# DPT2_3.net
KiCad netlist of a schematic drawn in Altium Designer
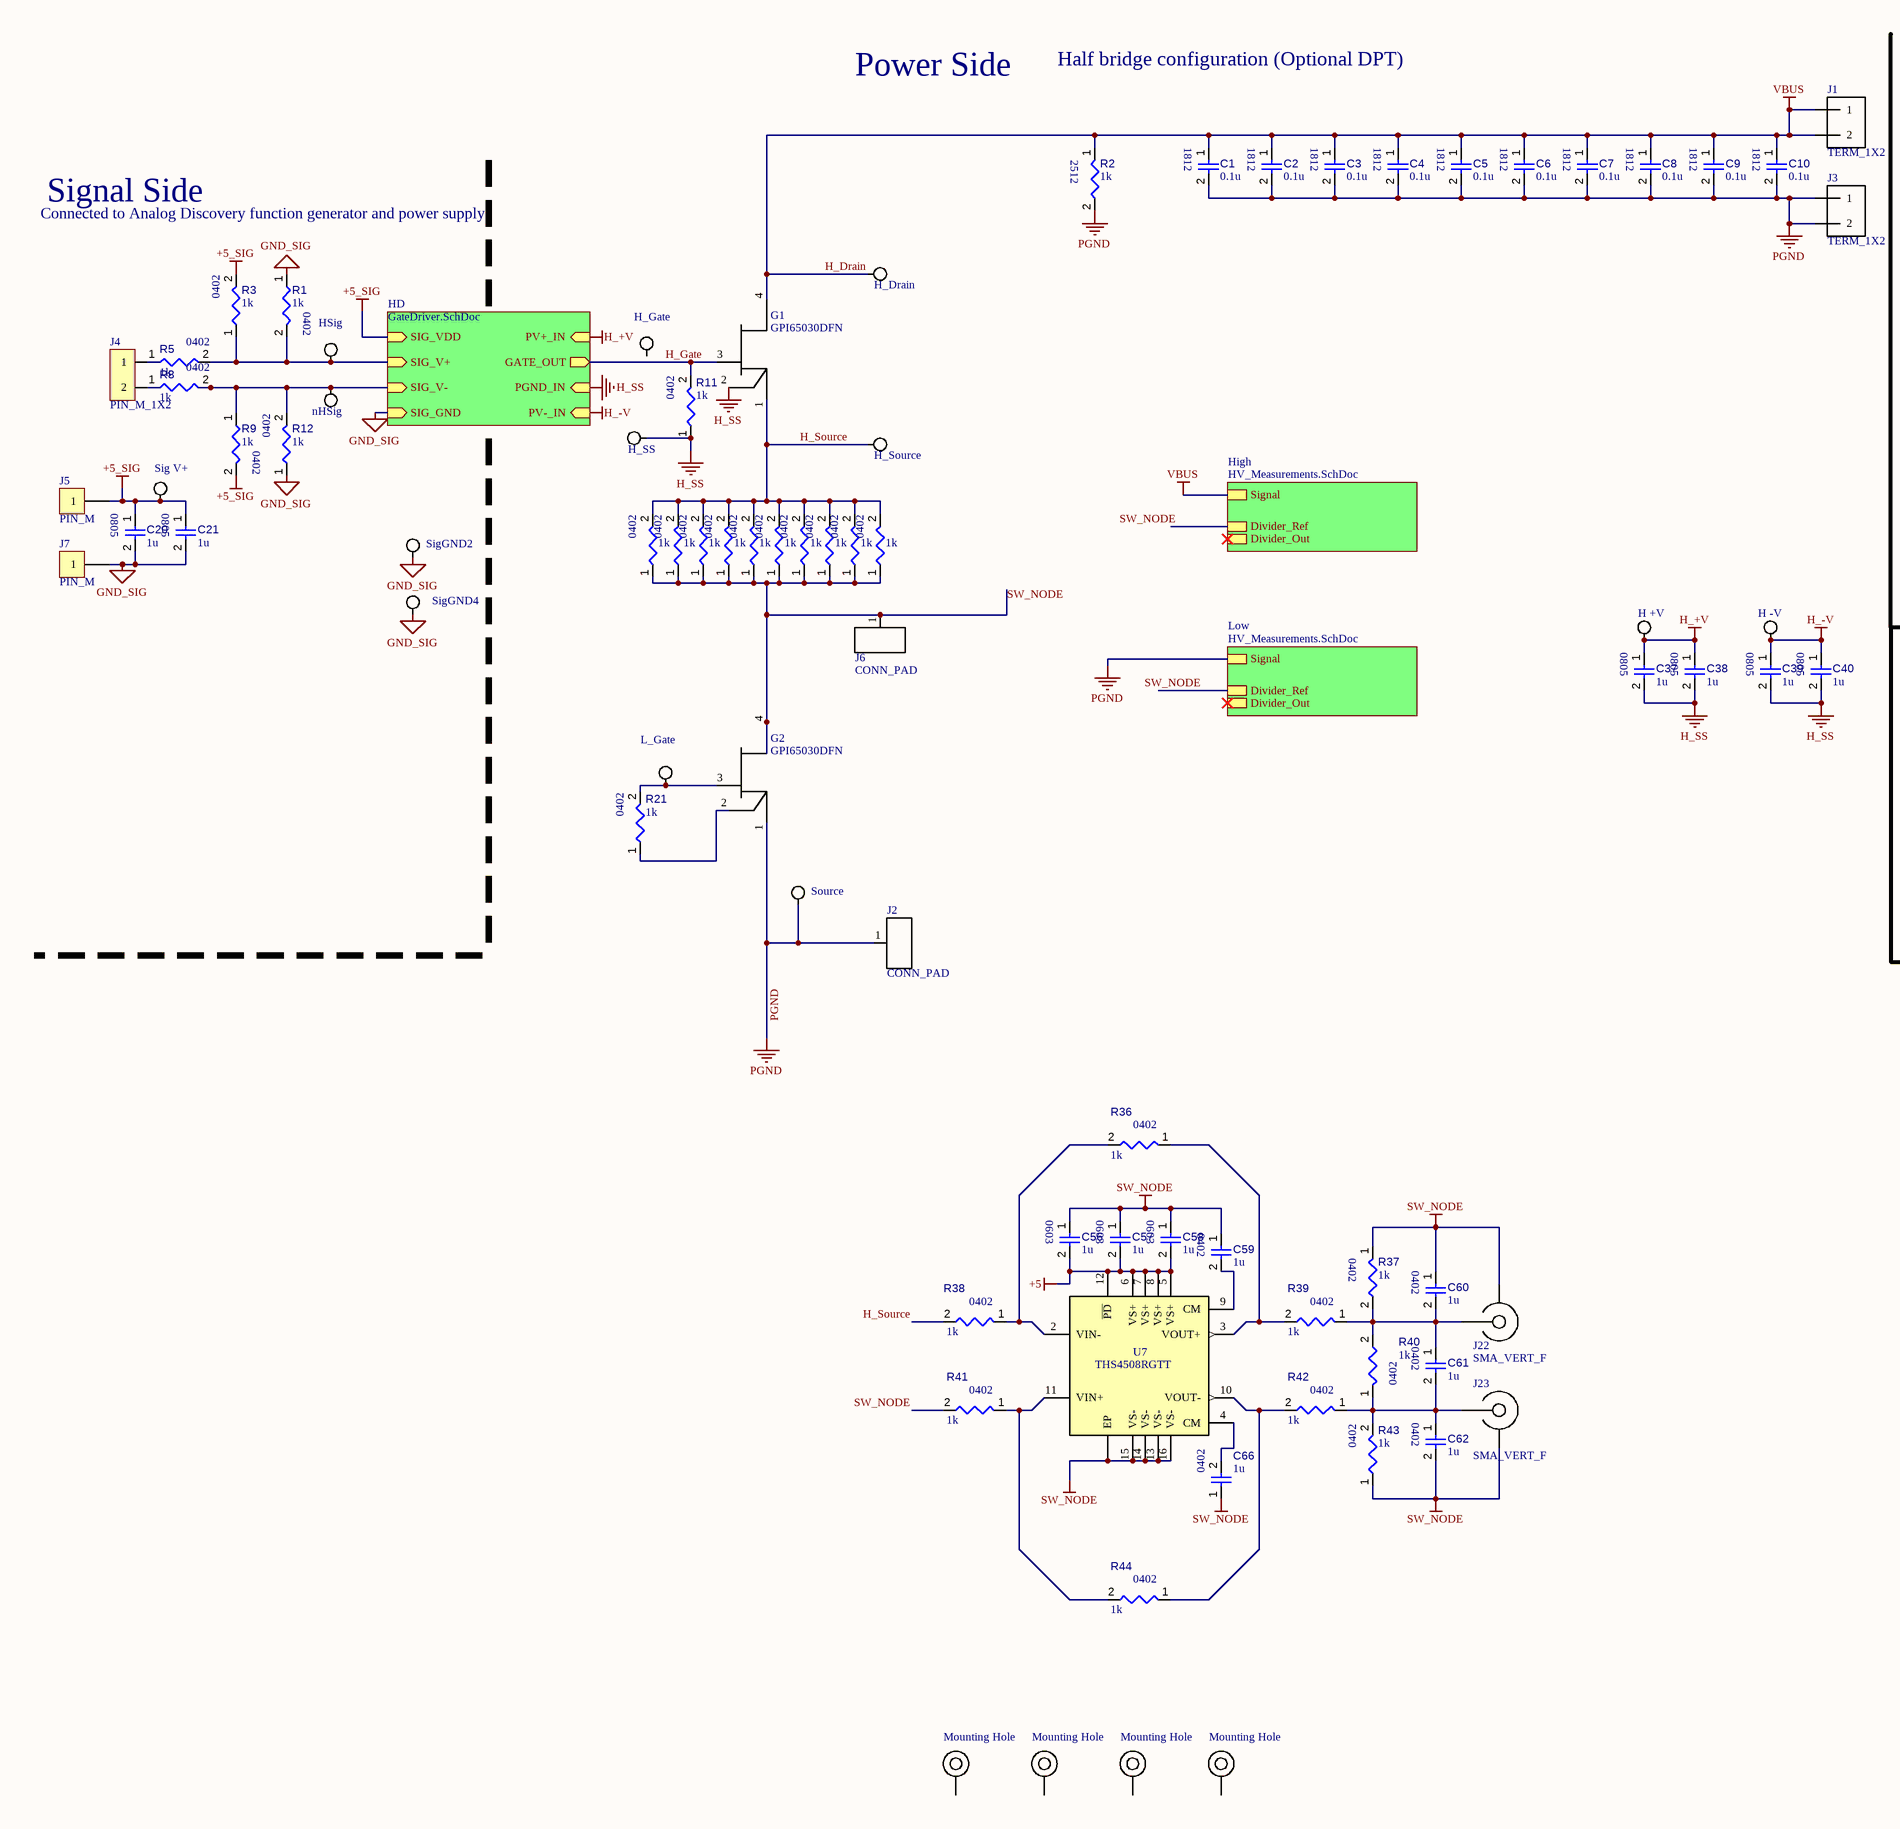
[diagram p0: DPT2.3.SchDoc, left]
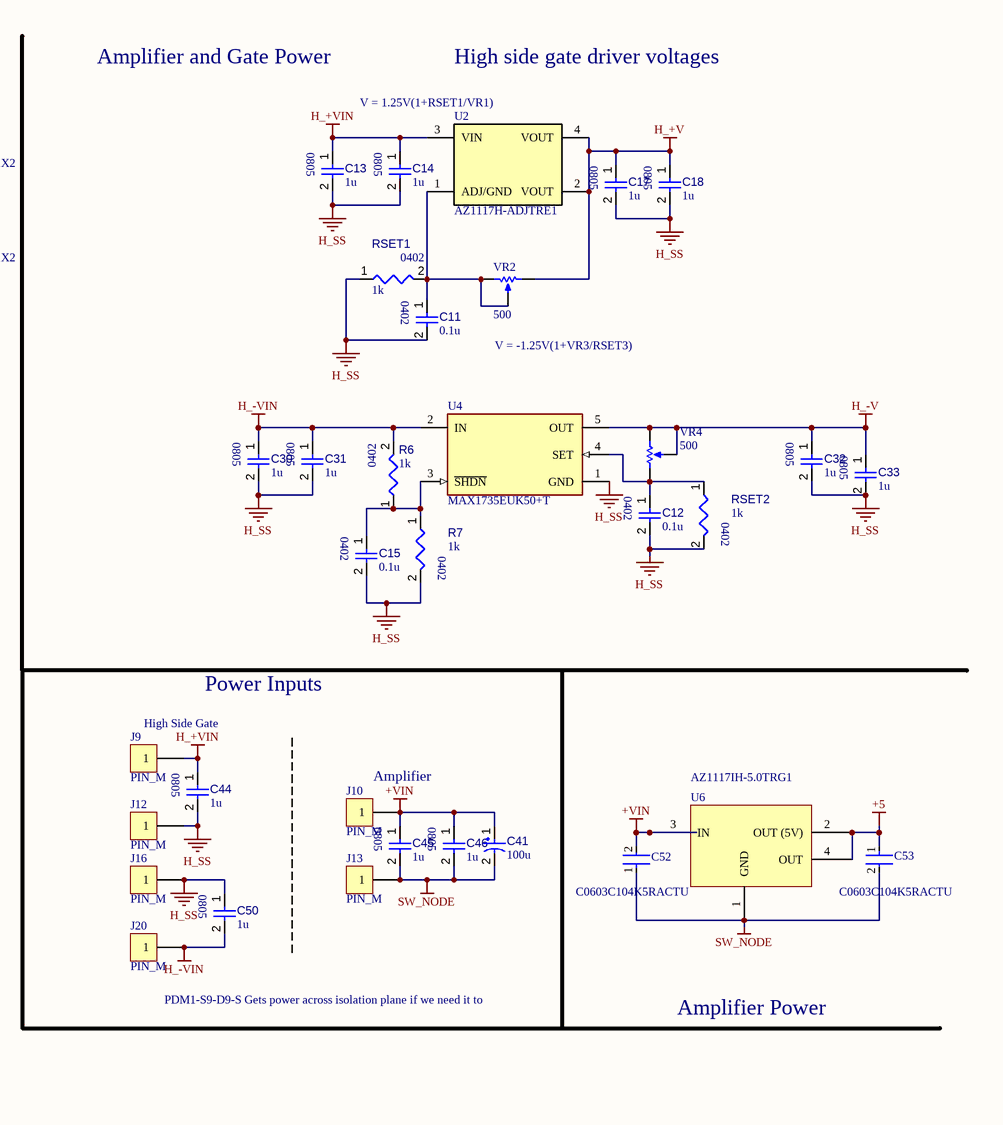
[diagram p1: DPT2.3.SchDoc, right]

(export (version "E")
  (design (tool "Eeschema 10.0.6"))
  (components
    (comp (ref "C1")
      (value "0.1u")
      (footprint "CAP_1812")
      (description "Non polarized SMD capacitor - 1812 (4532 Metric)")
      (fields (field (name "Comment") "CAP-1812"))
      (libsource (lib "2256-GaN Power") (part "CAP-NP-2"))
    )
    (comp (ref "C2")
      (value "0.1u")
      (footprint "CAP_1812")
      (description "Non polarized SMD capacitor - 1812 (4532 Metric)")
      (fields (field (name "Comment") "CAP-1812"))
      (libsource (lib "2256-GaN Power") (part "CAP-NP-2"))
    )
    (comp (ref "C3")
      (value "0.1u")
      (footprint "CAP_1812")
      (description "Non polarized SMD capacitor - 1812 (4532 Metric)")
      (fields (field (name "Comment") "CAP-1812"))
      (libsource (lib "2256-GaN Power") (part "CAP-NP-2"))
    )
    (comp (ref "C4")
      (value "0.1u")
      (footprint "CAP_1812")
      (description "Non polarized SMD capacitor - 1812 (4532 Metric)")
      (fields (field (name "Comment") "CAP-1812"))
      (libsource (lib "2256-GaN Power") (part "CAP-NP-2"))
    )
    (comp (ref "C5")
      (value "0.1u")
      (footprint "CAP_1812")
      (description "Non polarized SMD capacitor - 1812 (4532 Metric)")
      (fields (field (name "Comment") "CAP-1812"))
      (libsource (lib "2256-GaN Power") (part "CAP-NP-2"))
    )
    (comp (ref "C6")
      (value "0.1u")
      (footprint "CAP_1812")
      (description "Non polarized SMD capacitor - 1812 (4532 Metric)")
      (fields (field (name "Comment") "CAP-1812"))
      (libsource (lib "2256-GaN Power") (part "CAP-NP-2"))
    )
    (comp (ref "C7")
      (value "0.1u")
      (footprint "CAP_1812")
      (description "Non polarized SMD capacitor - 1812 (4532 Metric)")
      (fields (field (name "Comment") "CAP-1812"))
      (libsource (lib "2256-GaN Power") (part "CAP-NP-2"))
    )
    (comp (ref "C8")
      (value "0.1u")
      (footprint "CAP_1812")
      (description "Non polarized SMD capacitor - 1812 (4532 Metric)")
      (fields (field (name "Comment") "CAP-1812"))
      (libsource (lib "2256-GaN Power") (part "CAP-NP-2"))
    )
    (comp (ref "C9")
      (value "0.1u")
      (footprint "CAP_1812")
      (description "Non polarized SMD capacitor - 1812 (4532 Metric)")
      (fields (field (name "Comment") "CAP-1812"))
      (libsource (lib "2256-GaN Power") (part "CAP-NP-2"))
    )
    (comp (ref "C10")
      (value "0.1u")
      (footprint "CAP_1812")
      (description "Non polarized SMD capacitor - 1812 (4532 Metric)")
      (fields (field (name "Comment") "CAP-1812"))
      (libsource (lib "2256-GaN Power") (part "CAP-NP-2"))
    )
    (comp (ref "C11")
      (value "0.1u")
      (footprint "CAP_0402_HIGH")
      (description "Non polarized SMD capacitor - 0402 (1005 Metric)")
      (fields (field (name "Comment") "CAP-0402"))
      (libsource (lib "2256-GaN Power") (part "CAP-NP-2"))
    )
    (comp (ref "C12")
      (value "0.1u")
      (footprint "CAP_0402_HIGH")
      (description "Non polarized SMD capacitor - 0402 (1005 Metric)")
      (fields (field (name "Comment") "CAP-0402"))
      (libsource (lib "2256-GaN Power") (part "CAP-NP-2"))
    )
    (comp (ref "C13")
      (value "1u")
      (footprint "CAP_0805_MED")
      (description "Non polarized SMD capacitor - 0805 (1608 Metric)")
      (fields (field (name "Comment") "CAP-0805"))
      (libsource (lib "2256-GaN Power") (part "CAP-NP-2"))
    )
    (comp (ref "C14")
      (value "1u")
      (footprint "CAP_0805_MED")
      (description "Non polarized SMD capacitor - 0805 (1608 Metric)")
      (fields (field (name "Comment") "CAP-0805"))
      (libsource (lib "2256-GaN Power") (part "CAP-NP-2"))
    )
    (comp (ref "C15")
      (value "0.1u")
      (footprint "CAP_0402_HIGH")
      (description "Non polarized SMD capacitor - 0402 (1005 Metric)")
      (fields (field (name "Comment") "CAP-0402"))
      (libsource (lib "2256-GaN Power") (part "CAP-NP-2"))
    )
    (comp (ref "C17")
      (value "1u")
      (footprint "CAP_0805_MED")
      (description "Non polarized SMD capacitor - 0805 (1608 Metric)")
      (fields (field (name "Comment") "CAP-0805"))
      (libsource (lib "2256-GaN Power") (part "CAP-NP-2"))
    )
    (comp (ref "C18")
      (value "1u")
      (footprint "CAP_0805_MED")
      (description "Non polarized SMD capacitor - 0805 (1608 Metric)")
      (fields (field (name "Comment") "CAP-0805"))
      (libsource (lib "2256-GaN Power") (part "CAP-NP-2"))
    )
    (comp (ref "C20")
      (value "1u")
      (footprint "CAP_0805_MED")
      (description "Non polarized SMD capacitor - 0805 (1608 Metric)")
      (fields (field (name "Comment") "CAP-0805"))
      (libsource (lib "2256-GaN Power") (part "CAP-NP-2"))
    )
    (comp (ref "C21")
      (value "1u")
      (footprint "CAP_0805_MED")
      (description "Non polarized SMD capacitor - 0805 (1608 Metric)")
      (fields (field (name "Comment") "CAP-0805"))
      (libsource (lib "2256-GaN Power") (part "CAP-NP-2"))
    )
    (comp (ref "C30")
      (value "1u")
      (footprint "CAP_0805_MED")
      (description "Non polarized SMD capacitor - 0805 (1608 Metric)")
      (fields (field (name "Comment") "CAP-0805"))
      (libsource (lib "2256-GaN Power") (part "CAP-NP-2"))
    )
    (comp (ref "C31")
      (value "1u")
      (footprint "CAP_0805_MED")
      (description "Non polarized SMD capacitor - 0805 (1608 Metric)")
      (fields (field (name "Comment") "CAP-0805"))
      (libsource (lib "2256-GaN Power") (part "CAP-NP-2"))
    )
    (comp (ref "C32")
      (value "1u")
      (footprint "CAP_0805_MED")
      (description "Non polarized SMD capacitor - 0805 (1608 Metric)")
      (fields (field (name "Comment") "CAP-0805"))
      (libsource (lib "2256-GaN Power") (part "CAP-NP-2"))
    )
    (comp (ref "C33")
      (value "1u")
      (footprint "CAP_0805_MED")
      (description "Non polarized SMD capacitor - 0805 (1608 Metric)")
      (fields (field (name "Comment") "CAP-0805"))
      (libsource (lib "2256-GaN Power") (part "CAP-NP-2"))
    )
    (comp (ref "C37")
      (value "1u")
      (footprint "CAP_0805_MED")
      (description "Non polarized SMD capacitor - 0805 (1608 Metric)")
      (fields (field (name "Comment") "CAP-0805"))
      (libsource (lib "2256-GaN Power") (part "CAP-NP-2"))
    )
    (comp (ref "C38")
      (value "1u")
      (footprint "CAP_0805_MED")
      (description "Non polarized SMD capacitor - 0805 (1608 Metric)")
      (fields (field (name "Comment") "CAP-0805"))
      (libsource (lib "2256-GaN Power") (part "CAP-NP-2"))
    )
    (comp (ref "C39")
      (value "1u")
      (footprint "CAP_0805_MED")
      (description "Non polarized SMD capacitor - 0805 (1608 Metric)")
      (fields (field (name "Comment") "CAP-0805"))
      (libsource (lib "2256-GaN Power") (part "CAP-NP-2"))
    )
    (comp (ref "C40")
      (value "1u")
      (footprint "CAP_0805_MED")
      (description "Non polarized SMD capacitor - 0805 (1608 Metric)")
      (fields (field (name "Comment") "CAP-0805"))
      (libsource (lib "2256-GaN Power") (part "CAP-NP-2"))
    )
    (comp (ref "C41")
      (value "100u")
      (footprint "PCAP_2MM_5MM")
      (description "Polarized THT capacitor - Radial can, 2mm lead spacing, 5mm diameter")
      (fields (field (name "Comment") "PCAP-2MMx5MM"))
      (libsource (lib "2256-GaN Power") (part "CAP-P-2"))
    )
    (comp (ref "C44")
      (value "1u")
      (footprint "CAP_0805_MED")
      (description "Non polarized SMD capacitor - 0805 (1608 Metric)")
      (fields (field (name "Comment") "CAP-0805"))
      (libsource (lib "2256-GaN Power") (part "CAP-NP-2"))
    )
    (comp (ref "C45")
      (value "1u")
      (footprint "CAP_0805_MED")
      (description "Non polarized SMD capacitor - 0805 (1608 Metric)")
      (fields (field (name "Comment") "CAP-0805"))
      (libsource (lib "2256-GaN Power") (part "CAP-NP-2"))
    )
    (comp (ref "C46")
      (value "1u")
      (footprint "CAP_0805_MED")
      (description "Non polarized SMD capacitor - 0805 (1608 Metric)")
      (fields (field (name "Comment") "CAP-0805"))
      (libsource (lib "2256-GaN Power") (part "CAP-NP-2"))
    )
    (comp (ref "C50")
      (value "1u")
      (footprint "CAP_0805_MED")
      (description "Non polarized SMD capacitor - 0805 (1608 Metric)")
      (fields (field (name "Comment") "CAP-0805"))
      (libsource (lib "2256-GaN Power") (part "CAP-NP-2"))
    )
    (comp (ref "C52")
      (value "C0603C104K5RACTU")
      (footprint "FP-C0603C-CF-IPC_B")
      (description "CAP CER 0.1UF 50V X7R 0603")
      (fields (field (name "TOLERANCE") "0.1") (field (name "MANUFACTURER") "KEMET"))
      (libsource (lib "Altium Content Vault") (part "b4654b650e69147ec39a6b967a45e02"))
    )
    (comp (ref "C53")
      (value "C0603C104K5RACTU")
      (footprint "FP-C0603C-CF-IPC_B")
      (description "CAP CER 0.1UF 50V X7R 0603")
      (fields (field (name "TOLERANCE") "0.1") (field (name "MANUFACTURER") "KEMET"))
      (libsource (lib "Altium Content Vault") (part "b4654b650e69147ec39a6b967a45e02"))
    )
    (comp (ref "C56")
      (value "1u")
      (footprint "CAP_0603_HIGH")
      (description "Non polarized SMD capacitor - 0603 (1608 Metric)")
      (fields (field (name "Comment") "CAP-0603"))
      (libsource (lib "2256-GaN Power") (part "CAP-NP-2"))
    )
    (comp (ref "C57")
      (value "1u")
      (footprint "CAP_0603_HIGH")
      (description "Non polarized SMD capacitor - 0603 (1608 Metric)")
      (fields (field (name "Comment") "CAP-0603"))
      (libsource (lib "2256-GaN Power") (part "CAP-NP-2"))
    )
    (comp (ref "C58")
      (value "1u")
      (footprint "CAP_0603_HIGH")
      (description "Non polarized SMD capacitor - 0603 (1608 Metric)")
      (fields (field (name "Comment") "CAP-0603"))
      (libsource (lib "2256-GaN Power") (part "CAP-NP-2"))
    )
    (comp (ref "C59")
      (value "1u")
      (footprint "CAP_0402_HIGH")
      (description "Non polarized SMD capacitor - 0402 (1005 Metric)")
      (fields (field (name "Comment") "CAP-0402"))
      (libsource (lib "2256-GaN Power") (part "CAP-NP-2"))
    )
    (comp (ref "C60")
      (value "1u")
      (footprint "CAP_0402_HIGH")
      (description "Non polarized SMD capacitor - 0402 (1005 Metric)")
      (fields (field (name "Comment") "CAP-0402"))
      (libsource (lib "2256-GaN Power") (part "CAP-NP-2"))
    )
    (comp (ref "C61")
      (value "1u")
      (footprint "CAP_0402_HIGH")
      (description "Non polarized SMD capacitor - 0402 (1005 Metric)")
      (fields (field (name "Comment") "CAP-0402"))
      (libsource (lib "2256-GaN Power") (part "CAP-NP-2"))
    )
    (comp (ref "C62")
      (value "1u")
      (footprint "CAP_0402_HIGH")
      (description "Non polarized SMD capacitor - 0402 (1005 Metric)")
      (fields (field (name "Comment") "CAP-0402"))
      (libsource (lib "2256-GaN Power") (part "CAP-NP-2"))
    )
    (comp (ref "C66")
      (value "1u")
      (footprint "CAP_0402_HIGH")
      (description "Non polarized SMD capacitor - 0402 (1005 Metric)")
      (fields (field (name "Comment") "CAP-0402"))
      (libsource (lib "2256-GaN Power") (part "CAP-NP-2"))
    )
    (comp (ref "G1")
      (value "GPI65030DFN")
      (footprint "DFN_8X8")
      (description "650V 15A GaN Enhancement mode Transistor")
      (libsource (lib "2256-GaN Power") (part "TRANS_GPI65030DFN"))
    )
    (comp (ref "G2")
      (value "GPI65030DFN")
      (footprint "DFN_8X8")
      (description "650V 15A GaN Enhancement mode Transistor")
      (libsource (lib "2256-GaN Power") (part "TRANS_GPI65030DFN"))
    )
    (comp (ref "H +V")
      (value "Testpoint")
      (footprint "Testpoint-Footprint-1")
      (description "testpoint for circuit")
      (libsource (lib "2256-GaN Power") (part "Testpoint-Symbol-1"))
    )
    (comp (ref "H -V")
      (value "Testpoint")
      (footprint "Testpoint-Footprint-1")
      (description "testpoint for circuit")
      (libsource (lib "2256-GaN Power") (part "Testpoint-Symbol-1"))
    )
    (comp (ref "HSig")
      (value "Testpoint")
      (footprint "Testpoint-Footprint-1")
      (description "testpoint for circuit")
      (libsource (lib "2256-GaN Power") (part "Testpoint-Symbol-1"))
    )
    (comp (ref "H_Drain")
      (value "Testpoint")
      (footprint "Testpoint-Footprint-1")
      (description "testpoint for circuit")
      (libsource (lib "2256-GaN Power") (part "Testpoint-Symbol-1"))
    )
    (comp (ref "H_Gate")
      (value "Testpoint")
      (footprint "Testpoint-Footprint-1")
      (description "testpoint for circuit")
      (libsource (lib "2256-GaN Power") (part "Testpoint-Symbol-1"))
    )
    (comp (ref "H_Source")
      (value "Testpoint")
      (footprint "Testpoint-Footprint-1")
      (description "testpoint for circuit")
      (libsource (lib "2256-GaN Power") (part "Testpoint-Symbol-1"))
    )
    (comp (ref "H_SS")
      (value "Testpoint")
      (footprint "Testpoint-Footprint-1")
      (description "testpoint for circuit")
      (libsource (lib "2256-GaN Power") (part "Testpoint-Symbol-1"))
    )
    (comp (ref "J1")
      (value "TERM_1X2")
      (footprint "J_TERM_BLK_1X2")
      (description "Terminal Block 1X2, 6.35mm pitch")
      (libsource (lib "2256-GaN Power") (part "TERM_BLK_1X2"))
    )
    (comp (ref "J2")
      (value "CONN_PAD")
      (footprint "CONN_PAD")
      (description "Solderable Connection Pad")
      (libsource (lib "2256-GaN Power") (part "CONN_PAD"))
    )
    (comp (ref "J3")
      (value "TERM_1X2")
      (footprint "J_TERM_BLK_1X2")
      (description "Terminal Block 1X2, 6.35mm pitch")
      (libsource (lib "2256-GaN Power") (part "TERM_BLK_1X2"))
    )
    (comp (ref "J4")
      (value "PIN_M_1X2")
      (footprint "J_THT_2.54MM_1X2")
      (description "Male Pin 2.54mm pitch 1X2")
      (libsource (lib "2256-GaN Power") (part "M_PIN_HEAD_1X2"))
    )
    (comp (ref "J5")
      (value "PIN_M")
      (footprint "J_THT_1_PIN")
      (description "Male Pin, 1 Pin")
      (libsource (lib "2256-GaN Power") (part "M_PIN_HEAD_1X1"))
    )
    (comp (ref "J6")
      (value "CONN_PAD")
      (footprint "CONN_PAD")
      (description "Solderable Connection Pad")
      (libsource (lib "") (part "CONN_PAD_1"))
    )
    (comp (ref "J7")
      (value "PIN_M")
      (footprint "J_THT_1_PIN")
      (description "Male Pin, 1 Pin")
      (libsource (lib "2256-GaN Power") (part "M_PIN_HEAD_1X1"))
    )
    (comp (ref "J9")
      (value "PIN_M")
      (footprint "J_THT_1_PIN")
      (description "Male Pin, 1 Pin")
      (libsource (lib "2256-GaN Power") (part "M_PIN_HEAD_1X1"))
    )
    (comp (ref "J10")
      (value "PIN_M")
      (footprint "J_THT_1_PIN")
      (description "Male Pin, 1 Pin")
      (libsource (lib "2256-GaN Power") (part "M_PIN_HEAD_1X1"))
    )
    (comp (ref "J12")
      (value "PIN_M")
      (footprint "J_THT_1_PIN")
      (description "Male Pin, 1 Pin")
      (libsource (lib "2256-GaN Power") (part "M_PIN_HEAD_1X1"))
    )
    (comp (ref "J13")
      (value "PIN_M")
      (footprint "J_THT_1_PIN")
      (description "Male Pin, 1 Pin")
      (libsource (lib "2256-GaN Power") (part "M_PIN_HEAD_1X1"))
    )
    (comp (ref "J16")
      (value "PIN_M")
      (footprint "J_THT_1_PIN")
      (description "Male Pin, 1 Pin")
      (libsource (lib "2256-GaN Power") (part "M_PIN_HEAD_1X1"))
    )
    (comp (ref "J20")
      (value "PIN_M")
      (footprint "J_THT_1_PIN")
      (description "Male Pin, 1 Pin")
      (libsource (lib "2256-GaN Power") (part "M_PIN_HEAD_1X1"))
    )
    (comp (ref "J22")
      (value "SMA_VERT_F")
      (footprint "SMA_VERT_F")
      (description "SMA connector, Vertical, Female")
      (libsource (lib "") (part "SMA_F_1"))
    )
    (comp (ref "J23")
      (value "SMA_VERT_F")
      (footprint "SMA_VERT_F")
      (description "SMA connector, Vertical, Female")
      (libsource (lib "2256-GaN Power") (part "SMA_F"))
    )
    (comp (ref "L_Gate")
      (value "Testpoint")
      (footprint "Testpoint-Footprint-1")
      (description "testpoint for circuit")
      (libsource (lib "2256-GaN Power") (part "Testpoint-Symbol-1"))
    )
    (comp (ref "MH1")
      (value "Mounting Hole")
      (footprint "Mounting Hole-Footprint-1")
      (libsource (lib "2256-GaN Power") (part "Mounting Hole-Symbol-1"))
    )
    (comp (ref "MH2")
      (value "Mounting Hole")
      (footprint "Mounting Hole-Footprint-1")
      (libsource (lib "2256-GaN Power") (part "Mounting Hole-Symbol-1"))
    )
    (comp (ref "MH3")
      (value "Mounting Hole")
      (footprint "Mounting Hole-Footprint-1")
      (libsource (lib "2256-GaN Power") (part "Mounting Hole-Symbol-1"))
    )
    (comp (ref "MH4")
      (value "Mounting Hole")
      (footprint "Mounting Hole-Footprint-1")
      (libsource (lib "2256-GaN Power") (part "Mounting Hole-Symbol-1"))
    )
    (comp (ref "nHSig")
      (value "Testpoint")
      (footprint "Testpoint-Footprint-1")
      (description "testpoint for circuit")
      (libsource (lib "2256-GaN Power") (part "Testpoint-Symbol-1"))
    )
    (comp (ref "R1")
      (value "1k")
      (footprint "RES_0402_HIGH")
      (description "SMD Resistor - 0402 (1005 Metric)")
      (fields (field (name "Comment") "RES-0402"))
      (libsource (lib "2256-GaN Power") (part "RES-2"))
    )
    (comp (ref "R2")
      (value "1k")
      (footprint "RES_2512_MED")
      (description "SMD Resistor - 2512 (6432 Metric)")
      (fields (field (name "Comment") "RES-2512"))
      (libsource (lib "2256-GaN Power") (part "RES-2"))
    )
    (comp (ref "R3")
      (value "1k")
      (footprint "RES_0402_HIGH")
      (description "SMD Resistor - 0402 (1005 Metric)")
      (fields (field (name "Comment") "RES-0402"))
      (libsource (lib "2256-GaN Power") (part "RES-2"))
    )
    (comp (ref "R4")
      (value "1k")
      (footprint "RES_0402_HIGH")
      (description "SMD Resistor - 0402 (1005 Metric)")
      (fields (field (name "Comment") "RES-0402"))
      (libsource (lib "2256-GaN Power") (part "RES-2"))
    )
    (comp (ref "R5")
      (value "1k")
      (footprint "RES_0402_HIGH")
      (description "SMD Resistor - 0402 (1005 Metric)")
      (fields (field (name "Comment") "RES-0402"))
      (libsource (lib "2256-GaN Power") (part "RES-2"))
    )
    (comp (ref "R6")
      (value "1k")
      (footprint "RES_0402_HIGH")
      (description "SMD Resistor - 0402 (1005 Metric)")
      (fields (field (name "Comment") "RES-0402"))
      (libsource (lib "2256-GaN Power") (part "RES-2"))
    )
    (comp (ref "R7")
      (value "1k")
      (footprint "RES_0402_HIGH")
      (description "SMD Resistor - 0402 (1005 Metric)")
      (fields (field (name "Comment") "RES-0402"))
      (libsource (lib "2256-GaN Power") (part "RES-2"))
    )
    (comp (ref "R8")
      (value "1k")
      (footprint "RES_0402_HIGH")
      (description "SMD Resistor - 0402 (1005 Metric)")
      (fields (field (name "Comment") "RES-0402"))
      (libsource (lib "2256-GaN Power") (part "RES-2"))
    )
    (comp (ref "R9")
      (value "1k")
      (footprint "RES_0402_HIGH")
      (description "SMD Resistor - 0402 (1005 Metric)")
      (fields (field (name "Comment") "RES-0402"))
      (libsource (lib "2256-GaN Power") (part "RES-2"))
    )
    (comp (ref "R10")
      (value "1k")
      (footprint "RES_0402_HIGH")
      (description "SMD Resistor - 0402 (1005 Metric)")
      (fields (field (name "Comment") "RES-0402"))
      (libsource (lib "2256-GaN Power") (part "RES-2"))
    )
    (comp (ref "R11")
      (value "1k")
      (footprint "RES_0402_HIGH")
      (description "SMD Resistor - 0402 (1005 Metric)")
      (fields (field (name "Comment") "RES-0402"))
      (libsource (lib "2256-GaN Power") (part "RES-2"))
    )
    (comp (ref "R12")
      (value "1k")
      (footprint "RES_0402_HIGH")
      (description "SMD Resistor - 0402 (1005 Metric)")
      (fields (field (name "Comment") "RES-0402"))
      (libsource (lib "2256-GaN Power") (part "RES-2"))
    )
    (comp (ref "R21")
      (value "1k")
      (footprint "RES_0402_HIGH")
      (description "SMD Resistor - 0402 (1005 Metric)")
      (fields (field (name "Comment") "RES-0402"))
      (libsource (lib "2256-GaN Power") (part "RES-2"))
    )
    (comp (ref "R23")
      (value "1k")
      (footprint "RES_0402_HIGH")
      (description "SMD Resistor - 0402 (1005 Metric)")
      (fields (field (name "Comment") "RES-0402"))
      (libsource (lib "2256-GaN Power") (part "RES-2"))
    )
    (comp (ref "R25")
      (value "1k")
      (footprint "RES_0402_HIGH")
      (description "SMD Resistor - 0402 (1005 Metric)")
      (fields (field (name "Comment") "RES-0402"))
      (libsource (lib "2256-GaN Power") (part "RES-2"))
    )
    (comp (ref "R36")
      (value "1k")
      (footprint "RES_0402_HIGH")
      (description "SMD Resistor - 0402 (1005 Metric)")
      (fields (field (name "Comment") "RES-0402"))
      (libsource (lib "2256-GaN Power") (part "RES-2"))
    )
    (comp (ref "R37")
      (value "1k")
      (footprint "RES_0402_HIGH")
      (description "SMD Resistor - 0402 (1005 Metric)")
      (fields (field (name "Comment") "RES-0402"))
      (libsource (lib "2256-GaN Power") (part "RES-2"))
    )
    (comp (ref "R38")
      (value "1k")
      (footprint "RES_0402_HIGH")
      (description "SMD Resistor - 0402 (1005 Metric)")
      (fields (field (name "Comment") "RES-0402"))
      (libsource (lib "2256-GaN Power") (part "RES-2"))
    )
    (comp (ref "R39")
      (value "1k")
      (footprint "RES_0402_HIGH")
      (description "SMD Resistor - 0402 (1005 Metric)")
      (fields (field (name "Comment") "RES-0402"))
      (libsource (lib "2256-GaN Power") (part "RES-2"))
    )
    (comp (ref "R40")
      (value "1k")
      (footprint "RES_0402_HIGH")
      (description "SMD Resistor - 0402 (1005 Metric)")
      (fields (field (name "Comment") "RES-0402"))
      (libsource (lib "2256-GaN Power") (part "RES-2"))
    )
    (comp (ref "R41")
      (value "1k")
      (footprint "RES_0402_HIGH")
      (description "SMD Resistor - 0402 (1005 Metric)")
      (fields (field (name "Comment") "RES-0402"))
      (libsource (lib "2256-GaN Power") (part "RES-2"))
    )
    (comp (ref "R42")
      (value "1k")
      (footprint "RES_0402_HIGH")
      (description "SMD Resistor - 0402 (1005 Metric)")
      (fields (field (name "Comment") "RES-0402"))
      (libsource (lib "2256-GaN Power") (part "RES-2"))
    )
    (comp (ref "R43")
      (value "1k")
      (footprint "RES_0402_HIGH")
      (description "SMD Resistor - 0402 (1005 Metric)")
      (fields (field (name "Comment") "RES-0402"))
      (libsource (lib "2256-GaN Power") (part "RES-2"))
    )
    (comp (ref "R44")
      (value "1k")
      (footprint "RES_0402_HIGH")
      (description "SMD Resistor - 0402 (1005 Metric)")
      (fields (field (name "Comment") "RES-0402"))
      (libsource (lib "2256-GaN Power") (part "RES-2"))
    )
    (comp (ref "R45")
      (value "1k")
      (footprint "RES_0402_HIGH")
      (description "SMD Resistor - 0402 (1005 Metric)")
      (fields (field (name "Comment") "RES-0402"))
      (libsource (lib "2256-GaN Power") (part "RES-2"))
    )
    (comp (ref "R46")
      (value "1k")
      (footprint "RES_0402_HIGH")
      (description "SMD Resistor - 0402 (1005 Metric)")
      (fields (field (name "Comment") "RES-0402"))
      (libsource (lib "2256-GaN Power") (part "RES-2"))
    )
    (comp (ref "R47")
      (value "1k")
      (footprint "RES_0402_HIGH")
      (description "SMD Resistor - 0402 (1005 Metric)")
      (fields (field (name "Comment") "RES-0402"))
      (libsource (lib "2256-GaN Power") (part "RES-2"))
    )
    (comp (ref "R49")
      (value "1k")
      (footprint "RES_0402_HIGH")
      (description "SMD Resistor - 0402 (1005 Metric)")
      (fields (field (name "Comment") "RES-0402"))
      (libsource (lib "2256-GaN Power") (part "RES-2"))
    )
    (comp (ref "R50")
      (value "1k")
      (footprint "RES_0402_HIGH")
      (description "SMD Resistor - 0402 (1005 Metric)")
      (fields (field (name "Comment") "RES-0402"))
      (libsource (lib "2256-GaN Power") (part "RES-2"))
    )
    (comp (ref "R53")
      (value "1k")
      (footprint "RES_0402_HIGH")
      (description "SMD Resistor - 0402 (1005 Metric)")
      (fields (field (name "Comment") "RES-0402"))
      (libsource (lib "2256-GaN Power") (part "RES-2"))
    )
    (comp (ref "RSET1")
      (value "1k")
      (footprint "RES_0402_HIGH")
      (description "SMD Resistor - 0402 (1005 Metric)")
      (fields (field (name "Comment") "RES-0402"))
      (libsource (lib "2256-GaN Power") (part "RES-2"))
    )
    (comp (ref "RSET2")
      (value "1k")
      (footprint "RES_0402_HIGH")
      (description "SMD Resistor - 0402 (1005 Metric)")
      (fields (field (name "Comment") "RES-0402"))
      (libsource (lib "2256-GaN Power") (part "RES-2"))
    )
    (comp (ref "Sig V+")
      (value "Testpoint")
      (footprint "Testpoint-Footprint-1")
      (description "testpoint for circuit")
      (libsource (lib "2256-GaN Power") (part "Testpoint-Symbol-1"))
    )
    (comp (ref "SigGND2")
      (value "Testpoint")
      (footprint "Testpoint-Footprint-1")
      (description "testpoint for circuit")
      (libsource (lib "2256-GaN Power") (part "Testpoint-Symbol-1"))
    )
    (comp (ref "SigGND4")
      (value "Testpoint")
      (footprint "Testpoint-Footprint-1")
      (description "testpoint for circuit")
      (libsource (lib "2256-GaN Power") (part "Testpoint-Symbol-1"))
    )
    (comp (ref "Source")
      (value "Testpoint")
      (footprint "Testpoint-Footprint-1")
      (description "testpoint for circuit")
      (libsource (lib "2256-GaN Power") (part "Testpoint-Symbol-1"))
    )
    (comp (ref "U2")
      (value "AZ1117H-ADJTRE1")
      (footprint "SOT-223")
      (description "IC REG LINEAR POS ADJ 1A SOT223")
      (libsource (lib "2256-GaN Power") (part "AZ1117H-ADJTRE1"))
    )
    (comp (ref "U4")
      (value "MAX1735EUK50+T")
      (footprint "FP-U5-2-IPC_B")
      (description "IC REG LIN NEG ADJ 200MA SOT23-5")
      (libsource (lib "Altium Content Vault") (part "3fe5ddc4f403acdf696fd8e1856eecf"))
    )
    (comp (ref "U6")
      (value "AZ1117IH-5.0TRG1")
      (footprint "SOT230P700X180-4N")
      (description "https://www.digikey.ca/en/products/detail/diodes-incorporated/AZ1117IH-5-0TRG1/5699673")
      (libsource (lib "2256-GaN Power") (part "AZ1117IH-5.0TRG1-Symbol-1"))
    )
    (comp (ref "U7")
      (value "THS4508RGTT")
      (footprint "QFN-16")
      (description "WIDEBAND, LOW NOISE, LOW DISTORTION FULLY DIFFERENTIAL AMPLIFIER")
      (libsource (lib "2256-GaN Power") (part "THS4508"))
    )
    (comp (ref "VR2")
      (value "500")
      (footprint "TRIM_J-LEAD")
      (description "Potentiometer, J-Lead Trim Pot")
      (fields (field (name "Comment") "RES_POT_JLEAD"))
      (libsource (lib "2256-GaN Power") (part "RES-POT-3"))
    )
    (comp (ref "VR4")
      (value "500")
      (footprint "TRIM_J-LEAD")
      (description "Potentiometer, J-Lead Trim Pot")
      (fields (field (name "Comment") "RES_POT_JLEAD"))
      (libsource (lib "2256-GaN Power") (part "RES-POT-3"))
    )
  )
  (nets
    (net (code "1") (name "+5") (class "Default")
      (node (ref "C53") (pin "1") (pinfunction "1_1") (pintype "passive"))
      (node (ref "C56") (pin "2") (pinfunction "2_2") (pintype "passive"))
      (node (ref "C57") (pin "2") (pinfunction "2_2") (pintype "passive"))
      (node (ref "C58") (pin "2") (pinfunction "2_2") (pintype "passive"))
      (node (ref "U6") (pin "2") (pinfunction "OUT_(5V)_2") (pintype "passive"))
      (node (ref "U6") (pin "4") (pinfunction "OUT_4") (pintype "passive"))
      (node (ref "U7") (pin "12") (pinfunction "~{PD}_12") (pintype "passive"))
      (node (ref "U7") (pin "5") (pinfunction "VS+_5") (pintype "power_in"))
      (node (ref "U7") (pin "6") (pinfunction "VS+_6") (pintype "power_in"))
      (node (ref "U7") (pin "7") (pinfunction "VS+_7") (pintype "power_in"))
      (node (ref "U7") (pin "8") (pinfunction "VS+_8") (pintype "power_in"))
    )
    (net (code "2") (name "+5_SIG") (class "Default")
      (node (ref "C20") (pin "1") (pinfunction "1_1") (pintype "passive"))
      (node (ref "C21") (pin "1") (pinfunction "1_1") (pintype "passive"))
      (node (ref "J5") (pin "1") (pinfunction "1_1") (pintype "passive"))
      (node (ref "R3") (pin "2") (pinfunction "2_2") (pintype "passive"))
      (node (ref "R9") (pin "2") (pinfunction "2_2") (pintype "passive"))
      (node (ref "Sig V+") (pin "1") (pinfunction "1_1") (pintype "passive"))
    )
    (net (code "3") (name "+VIN") (class "Default")
      (node (ref "C41") (pin "1") (pinfunction "1_1") (pintype "passive"))
      (node (ref "C45") (pin "1") (pinfunction "1_1") (pintype "passive"))
      (node (ref "C46") (pin "1") (pinfunction "1_1") (pintype "passive"))
      (node (ref "C52") (pin "2") (pinfunction "2_2") (pintype "passive"))
      (node (ref "J10") (pin "1") (pinfunction "1_1") (pintype "passive"))
      (node (ref "U6") (pin "3") (pinfunction "IN_3") (pintype "passive"))
    )
    (net (code "6") (name "/H_Gate") (class "Default")
      (node (ref "G1") (pin "3") (pinfunction "G_3") (pintype "passive"))
      (node (ref "R11") (pin "2") (pinfunction "2_2") (pintype "passive"))
    )
    (net (code "7") (name "/H_Source") (class "Default")
      (node (ref "G1") (pin "1") (pinfunction "S_1") (pintype "passive"))
      (node (ref "H_Source") (pin "1") (pinfunction "1_1") (pintype "passive"))
      (node (ref "R10") (pin "2") (pinfunction "2_2") (pintype "passive"))
      (node (ref "R23") (pin "2") (pinfunction "2_2") (pintype "passive"))
      (node (ref "R25") (pin "2") (pinfunction "2_2") (pintype "passive"))
      (node (ref "R38") (pin "2") (pinfunction "2_2") (pintype "passive"))
      (node (ref "R4") (pin "2") (pinfunction "2_2") (pintype "passive"))
      (node (ref "R45") (pin "2") (pinfunction "2_2") (pintype "passive"))
      (node (ref "R46") (pin "2") (pinfunction "2_2") (pintype "passive"))
      (node (ref "R47") (pin "2") (pinfunction "2_2") (pintype "passive"))
      (node (ref "R49") (pin "2") (pinfunction "2_2") (pintype "passive"))
      (node (ref "R50") (pin "2") (pinfunction "2_2") (pintype "passive"))
      (node (ref "R53") (pin "2") (pinfunction "2_2") (pintype "passive"))
    )
    (net (code "8") (name "/SIG_V+") (class "Default")
      (node (ref "HSig") (pin "1") (pinfunction "1_1") (pintype "passive"))
      (node (ref "R1") (pin "2") (pinfunction "2_2") (pintype "passive"))
      (node (ref "R3") (pin "1") (pinfunction "1_1") (pintype "passive"))
      (node (ref "R5") (pin "2") (pinfunction "2_2") (pintype "passive"))
    )
    (net (code "9") (name "/SIG_V-") (class "Default")
      (node (ref "R12") (pin "2") (pinfunction "2_2") (pintype "passive"))
      (node (ref "R8") (pin "2") (pinfunction "2_2") (pintype "passive"))
      (node (ref "R9") (pin "1") (pinfunction "1_1") (pintype "passive"))
      (node (ref "nHSig") (pin "1") (pinfunction "1_1") (pintype "passive"))
    )
    (net (code "10") (name "GND_SIG") (class "Default")
      (node (ref "C20") (pin "2") (pinfunction "2_2") (pintype "passive"))
      (node (ref "C21") (pin "2") (pinfunction "2_2") (pintype "passive"))
      (node (ref "J7") (pin "1") (pinfunction "1_1") (pintype "passive"))
      (node (ref "R1") (pin "1") (pinfunction "1_1") (pintype "passive"))
      (node (ref "R12") (pin "1") (pinfunction "1_1") (pintype "passive"))
      (node (ref "SigGND2") (pin "1") (pinfunction "1_1") (pintype "passive"))
      (node (ref "SigGND4") (pin "1") (pinfunction "1_1") (pintype "passive"))
    )
    (net (code "11") (name "H_+V") (class "Default")
      (node (ref "C17") (pin "1") (pinfunction "1_1") (pintype "passive"))
      (node (ref "C18") (pin "1") (pinfunction "1_1") (pintype "passive"))
      (node (ref "C37") (pin "1") (pinfunction "1_1") (pintype "passive"))
      (node (ref "C38") (pin "1") (pinfunction "1_1") (pintype "passive"))
      (node (ref "H +V") (pin "1") (pinfunction "1_1") (pintype "passive"))
      (node (ref "U2") (pin "2") (pinfunction "VOUT_2") (pintype "passive"))
      (node (ref "U2") (pin "4") (pinfunction "VOUT_4") (pintype "passive"))
      (node (ref "VR2") (pin "1") (pinfunction "CCW_1") (pintype "passive"))
    )
    (net (code "12") (name "H_+VIN") (class "Default")
      (node (ref "C13") (pin "1") (pinfunction "1_1") (pintype "passive"))
      (node (ref "C14") (pin "1") (pinfunction "1_1") (pintype "passive"))
      (node (ref "C44") (pin "1") (pinfunction "1_1") (pintype "passive"))
      (node (ref "J9") (pin "1") (pinfunction "1_1") (pintype "passive"))
      (node (ref "U2") (pin "3") (pinfunction "VIN_3") (pintype "passive"))
    )
    (net (code "13") (name "H_-V") (class "Default")
      (node (ref "C32") (pin "1") (pinfunction "1_1") (pintype "passive"))
      (node (ref "C33") (pin "1") (pinfunction "1_1") (pintype "passive"))
      (node (ref "C39") (pin "1") (pinfunction "1_1") (pintype "passive"))
      (node (ref "C40") (pin "1") (pinfunction "1_1") (pintype "passive"))
      (node (ref "H -V") (pin "1") (pinfunction "1_1") (pintype "passive"))
      (node (ref "U4") (pin "5") (pinfunction "OUT_5") (pintype "passive"))
      (node (ref "VR4") (pin "2") (pinfunction "S_2") (pintype "passive"))
      (node (ref "VR4") (pin "3") (pinfunction "CW_3") (pintype "passive"))
    )
    (net (code "14") (name "H_-VIN") (class "Default")
      (node (ref "C30") (pin "1") (pinfunction "1_1") (pintype "passive"))
      (node (ref "C31") (pin "1") (pinfunction "1_1") (pintype "passive"))
      (node (ref "C50") (pin "2") (pinfunction "2_2") (pintype "passive"))
      (node (ref "J20") (pin "1") (pinfunction "1_1") (pintype "passive"))
      (node (ref "R6") (pin "2") (pinfunction "2_2") (pintype "passive"))
      (node (ref "U4") (pin "2") (pinfunction "IN_2") (pintype "power_in"))
    )
    (net (code "15") (name "H_SS") (class "Default")
      (node (ref "C11") (pin "2") (pinfunction "2_2") (pintype "passive"))
      (node (ref "C12") (pin "2") (pinfunction "2_2") (pintype "passive"))
      (node (ref "C13") (pin "2") (pinfunction "2_2") (pintype "passive"))
      (node (ref "C14") (pin "2") (pinfunction "2_2") (pintype "passive"))
      (node (ref "C15") (pin "2") (pinfunction "2_2") (pintype "passive"))
      (node (ref "C17") (pin "2") (pinfunction "2_2") (pintype "passive"))
      (node (ref "C18") (pin "2") (pinfunction "2_2") (pintype "passive"))
      (node (ref "C30") (pin "2") (pinfunction "2_2") (pintype "passive"))
      (node (ref "C31") (pin "2") (pinfunction "2_2") (pintype "passive"))
      (node (ref "C32") (pin "2") (pinfunction "2_2") (pintype "passive"))
      (node (ref "C33") (pin "2") (pinfunction "2_2") (pintype "passive"))
      (node (ref "C37") (pin "2") (pinfunction "2_2") (pintype "passive"))
      (node (ref "C38") (pin "2") (pinfunction "2_2") (pintype "passive"))
      (node (ref "C39") (pin "2") (pinfunction "2_2") (pintype "passive"))
      (node (ref "C40") (pin "2") (pinfunction "2_2") (pintype "passive"))
      (node (ref "C44") (pin "2") (pinfunction "2_2") (pintype "passive"))
      (node (ref "C50") (pin "1") (pinfunction "1_1") (pintype "passive"))
      (node (ref "G1") (pin "2") (pinfunction "KS_2") (pintype "passive"))
      (node (ref "H_SS") (pin "1") (pinfunction "1_1") (pintype "passive"))
      (node (ref "J12") (pin "1") (pinfunction "1_1") (pintype "passive"))
      (node (ref "J16") (pin "1") (pinfunction "1_1") (pintype "passive"))
      (node (ref "R11") (pin "1") (pinfunction "1_1") (pintype "passive"))
      (node (ref "R7") (pin "2") (pinfunction "2_2") (pintype "passive"))
      (node (ref "RSET1") (pin "1") (pinfunction "1_1") (pintype "passive"))
      (node (ref "RSET2") (pin "2") (pinfunction "2_2") (pintype "passive"))
      (node (ref "U4") (pin "1") (pinfunction "GND_1") (pintype "power_in"))
    )
    (net (code "16") (name "Net-(C59-Pad2)") (class "Default")
      (node (ref "C59") (pin "2") (pinfunction "2_2") (pintype "passive"))
      (node (ref "U7") (pin "9") (pinfunction "CM_9") (pintype "passive"))
    )
    (net (code "17") (name "Net-(C60-Pad2)") (class "Default")
      (node (ref "C60") (pin "2") (pinfunction "2_2") (pintype "passive"))
      (node (ref "C61") (pin "1") (pinfunction "1_1") (pintype "passive"))
      (node (ref "J22") (pin "1") (pinfunction "1_1") (pintype "passive"))
      (node (ref "R37") (pin "2") (pinfunction "2_2") (pintype "passive"))
      (node (ref "R39") (pin "1") (pinfunction "1_1") (pintype "passive"))
      (node (ref "R40") (pin "2") (pinfunction "2_2") (pintype "passive"))
    )
    (net (code "18") (name "Net-(C61-Pad2)") (class "Default")
      (node (ref "C61") (pin "2") (pinfunction "2_2") (pintype "passive"))
      (node (ref "C62") (pin "1") (pinfunction "1_1") (pintype "passive"))
      (node (ref "J23") (pin "1") (pinfunction "1_1") (pintype "passive"))
      (node (ref "R40") (pin "1") (pinfunction "1_1") (pintype "passive"))
      (node (ref "R42") (pin "1") (pinfunction "1_1") (pintype "passive"))
      (node (ref "R43") (pin "2") (pinfunction "2_2") (pintype "passive"))
    )
    (net (code "19") (name "Net-(C66-Pad2)") (class "Default")
      (node (ref "C66") (pin "2") (pinfunction "2_2") (pintype "passive"))
      (node (ref "U7") (pin "4") (pinfunction "CM_4") (pintype "passive"))
    )
    (net (code "20") (name "Net-(G2-G)") (class "Default")
      (node (ref "G2") (pin "3") (pinfunction "G_3") (pintype "passive"))
      (node (ref "L_Gate") (pin "1") (pinfunction "1_1") (pintype "passive"))
      (node (ref "R21") (pin "2") (pinfunction "2_2") (pintype "passive"))
    )
    (net (code "21") (name "Net-(G2-KS)") (class "Default")
      (node (ref "G2") (pin "2") (pinfunction "KS_2") (pintype "passive"))
      (node (ref "R21") (pin "1") (pinfunction "1_1") (pintype "passive"))
    )
    (net (code "22") (name "Net-(J4-Pad1)") (class "Default")
      (node (ref "J4") (pin "1") (pinfunction "1_1") (pintype "passive"))
      (node (ref "R5") (pin "1") (pinfunction "1_1") (pintype "passive"))
    )
    (net (code "23") (name "Net-(J4-Pad2)") (class "Default")
      (node (ref "J4") (pin "2") (pinfunction "2_2") (pintype "passive"))
      (node (ref "R8") (pin "1") (pinfunction "1_1") (pintype "passive"))
    )
    (net (code "24") (name "Net-(U2-ADJ{slash}GND)") (class "Default")
      (node (ref "C11") (pin "1") (pinfunction "1_1") (pintype "passive"))
      (node (ref "RSET1") (pin "2") (pinfunction "2_2") (pintype "passive"))
      (node (ref "U2") (pin "1") (pinfunction "ADJ/GND_1") (pintype "passive"))
      (node (ref "VR2") (pin "2") (pinfunction "S_2") (pintype "passive"))
      (node (ref "VR2") (pin "3") (pinfunction "CW_3") (pintype "passive"))
    )
    (net (code "25") (name "Net-(U4-SET)") (class "Default")
      (node (ref "C12") (pin "1") (pinfunction "1_1") (pintype "passive"))
      (node (ref "RSET2") (pin "1") (pinfunction "1_1") (pintype "passive"))
      (node (ref "U4") (pin "4") (pinfunction "SET_4") (pintype "input"))
      (node (ref "VR4") (pin "1") (pinfunction "CCW_1") (pintype "passive"))
    )
    (net (code "26") (name "Net-(U4-~{SHDN})") (class "Default")
      (node (ref "C15") (pin "1") (pinfunction "1_1") (pintype "passive"))
      (node (ref "R6") (pin "1") (pinfunction "1_1") (pintype "passive"))
      (node (ref "R7") (pin "1") (pinfunction "1_1") (pintype "passive"))
      (node (ref "U4") (pin "3") (pinfunction "~{SHDN}_3") (pintype "input"))
    )
    (net (code "27") (name "Net-(U7-VIN+)") (class "Default")
      (node (ref "R41") (pin "1") (pinfunction "1_1") (pintype "passive"))
      (node (ref "R44") (pin "2") (pinfunction "2_2") (pintype "passive"))
      (node (ref "U7") (pin "11") (pinfunction "VIN+_11") (pintype "passive"))
    )
    (net (code "28") (name "Net-(U7-VIN-)") (class "Default")
      (node (ref "R36") (pin "2") (pinfunction "2_2") (pintype "passive"))
      (node (ref "R38") (pin "1") (pinfunction "1_1") (pintype "passive"))
      (node (ref "U7") (pin "2") (pinfunction "VIN-_2") (pintype "passive"))
    )
    (net (code "29") (name "Net-(U7-VOUT+)") (class "Default")
      (node (ref "R36") (pin "1") (pinfunction "1_1") (pintype "passive"))
      (node (ref "R39") (pin "2") (pinfunction "2_2") (pintype "passive"))
      (node (ref "U7") (pin "3") (pinfunction "VOUT+_3") (pintype "output"))
    )
    (net (code "30") (name "Net-(U7-VOUT-)") (class "Default")
      (node (ref "R42") (pin "2") (pinfunction "2_2") (pintype "passive"))
      (node (ref "R44") (pin "1") (pinfunction "1_1") (pintype "passive"))
      (node (ref "U7") (pin "10") (pinfunction "VOUT-_10") (pintype "output"))
    )
    (net (code "31") (name "PGND") (class "Default")
      (node (ref "C1") (pin "2") (pinfunction "2_2") (pintype "passive"))
      (node (ref "C10") (pin "2") (pinfunction "2_2") (pintype "passive"))
      (node (ref "C2") (pin "2") (pinfunction "2_2") (pintype "passive"))
      (node (ref "C3") (pin "2") (pinfunction "2_2") (pintype "passive"))
      (node (ref "C4") (pin "2") (pinfunction "2_2") (pintype "passive"))
      (node (ref "C5") (pin "2") (pinfunction "2_2") (pintype "passive"))
      (node (ref "C6") (pin "2") (pinfunction "2_2") (pintype "passive"))
      (node (ref "C7") (pin "2") (pinfunction "2_2") (pintype "passive"))
      (node (ref "C8") (pin "2") (pinfunction "2_2") (pintype "passive"))
      (node (ref "C9") (pin "2") (pinfunction "2_2") (pintype "passive"))
      (node (ref "G2") (pin "1") (pinfunction "S_1") (pintype "passive"))
      (node (ref "J2") (pin "1") (pinfunction "1_1") (pintype "passive"))
      (node (ref "J3") (pin "1") (pinfunction "1_1") (pintype "passive"))
      (node (ref "J3") (pin "2") (pinfunction "2_2") (pintype "passive"))
      (node (ref "R2") (pin "2") (pinfunction "2_2") (pintype "passive"))
      (node (ref "Source") (pin "1") (pinfunction "1_1") (pintype "passive"))
    )
    (net (code "32") (name "SW_NODE") (class "Default")
      (node (ref "C41") (pin "2") (pinfunction "2_2") (pintype "passive"))
      (node (ref "C45") (pin "2") (pinfunction "2_2") (pintype "passive"))
      (node (ref "C46") (pin "2") (pinfunction "2_2") (pintype "passive"))
      (node (ref "C52") (pin "1") (pinfunction "1_1") (pintype "passive"))
      (node (ref "C53") (pin "2") (pinfunction "2_2") (pintype "passive"))
      (node (ref "C56") (pin "1") (pinfunction "1_1") (pintype "passive"))
      (node (ref "C57") (pin "1") (pinfunction "1_1") (pintype "passive"))
      (node (ref "C58") (pin "1") (pinfunction "1_1") (pintype "passive"))
      (node (ref "C59") (pin "1") (pinfunction "1_1") (pintype "passive"))
      (node (ref "C60") (pin "1") (pinfunction "1_1") (pintype "passive"))
      (node (ref "C62") (pin "2") (pinfunction "2_2") (pintype "passive"))
      (node (ref "C66") (pin "1") (pinfunction "1_1") (pintype "passive"))
      (node (ref "G2") (pin "4") (pinfunction "D_4") (pintype "passive"))
      (node (ref "J13") (pin "1") (pinfunction "1_1") (pintype "passive"))
      (node (ref "J22") (pin "2") (pinfunction "2_2") (pintype "passive"))
      (node (ref "J23") (pin "2") (pinfunction "2_2") (pintype "passive"))
      (node (ref "J6") (pin "1") (pinfunction "1_1") (pintype "passive"))
      (node (ref "R10") (pin "1") (pinfunction "1_1") (pintype "passive"))
      (node (ref "R23") (pin "1") (pinfunction "1_1") (pintype "passive"))
      (node (ref "R25") (pin "1") (pinfunction "1_1") (pintype "passive"))
      (node (ref "R37") (pin "1") (pinfunction "1_1") (pintype "passive"))
      (node (ref "R4") (pin "1") (pinfunction "1_1") (pintype "passive"))
      (node (ref "R41") (pin "2") (pinfunction "2_2") (pintype "passive"))
      (node (ref "R43") (pin "1") (pinfunction "1_1") (pintype "passive"))
      (node (ref "R45") (pin "1") (pinfunction "1_1") (pintype "passive"))
      (node (ref "R46") (pin "1") (pinfunction "1_1") (pintype "passive"))
      (node (ref "R47") (pin "1") (pinfunction "1_1") (pintype "passive"))
      (node (ref "R49") (pin "1") (pinfunction "1_1") (pintype "passive"))
      (node (ref "R50") (pin "1") (pinfunction "1_1") (pintype "passive"))
      (node (ref "R53") (pin "1") (pinfunction "1_1") (pintype "passive"))
      (node (ref "U6") (pin "1") (pinfunction "GND_1") (pintype "passive"))
      (node (ref "U7") (pin "13") (pinfunction "VS-_13") (pintype "power_in"))
      (node (ref "U7") (pin "14") (pinfunction "VS-_14") (pintype "power_in"))
      (node (ref "U7") (pin "15") (pinfunction "VS-_15") (pintype "power_in"))
      (node (ref "U7") (pin "16") (pinfunction "VS-_16") (pintype "power_in"))
      (node (ref "U7") (pin "17") (pinfunction "EP_17") (pintype "power_in"))
    )
    (net (code "33") (name "VBUS") (class "Default")
      (node (ref "C1") (pin "1") (pinfunction "1_1") (pintype "passive"))
      (node (ref "C10") (pin "1") (pinfunction "1_1") (pintype "passive"))
      (node (ref "C2") (pin "1") (pinfunction "1_1") (pintype "passive"))
      (node (ref "C3") (pin "1") (pinfunction "1_1") (pintype "passive"))
      (node (ref "C4") (pin "1") (pinfunction "1_1") (pintype "passive"))
      (node (ref "C5") (pin "1") (pinfunction "1_1") (pintype "passive"))
      (node (ref "C6") (pin "1") (pinfunction "1_1") (pintype "passive"))
      (node (ref "C7") (pin "1") (pinfunction "1_1") (pintype "passive"))
      (node (ref "C8") (pin "1") (pinfunction "1_1") (pintype "passive"))
      (node (ref "C9") (pin "1") (pinfunction "1_1") (pintype "passive"))
      (node (ref "G1") (pin "4") (pinfunction "D_4") (pintype "passive"))
      (node (ref "H_Drain") (pin "1") (pinfunction "1_1") (pintype "passive"))
      (node (ref "J1") (pin "1") (pinfunction "1_1") (pintype "passive"))
      (node (ref "J1") (pin "2") (pinfunction "2_2") (pintype "passive"))
      (node (ref "R2") (pin "1") (pinfunction "1_1") (pintype "passive"))
    )
    (net (code "34") (name "unconnected-(H_Gate-Pad1)") (class "Default")
      (node (ref "H_Gate") (pin "1") (pinfunction "1_1") (pintype "passive"))
    )
    (net (code "35") (name "unconnected-(MH1-GND-Pad1)") (class "Default")
      (node (ref "MH1") (pin "1") (pinfunction "GND_1") (pintype "passive"))
    )
    (net (code "36") (name "unconnected-(MH2-GND-Pad1)") (class "Default")
      (node (ref "MH2") (pin "1") (pinfunction "GND_1") (pintype "passive"))
    )
    (net (code "37") (name "unconnected-(MH3-GND-Pad1)") (class "Default")
      (node (ref "MH3") (pin "1") (pinfunction "GND_1") (pintype "passive"))
    )
    (net (code "38") (name "unconnected-(MH4-GND-Pad1)") (class "Default")
      (node (ref "MH4") (pin "1") (pinfunction "GND_1") (pintype "passive"))
    )
  )
)
